# obc-v2_POWER.net
KiCad netlist of a schematic drawn in Altium Designer
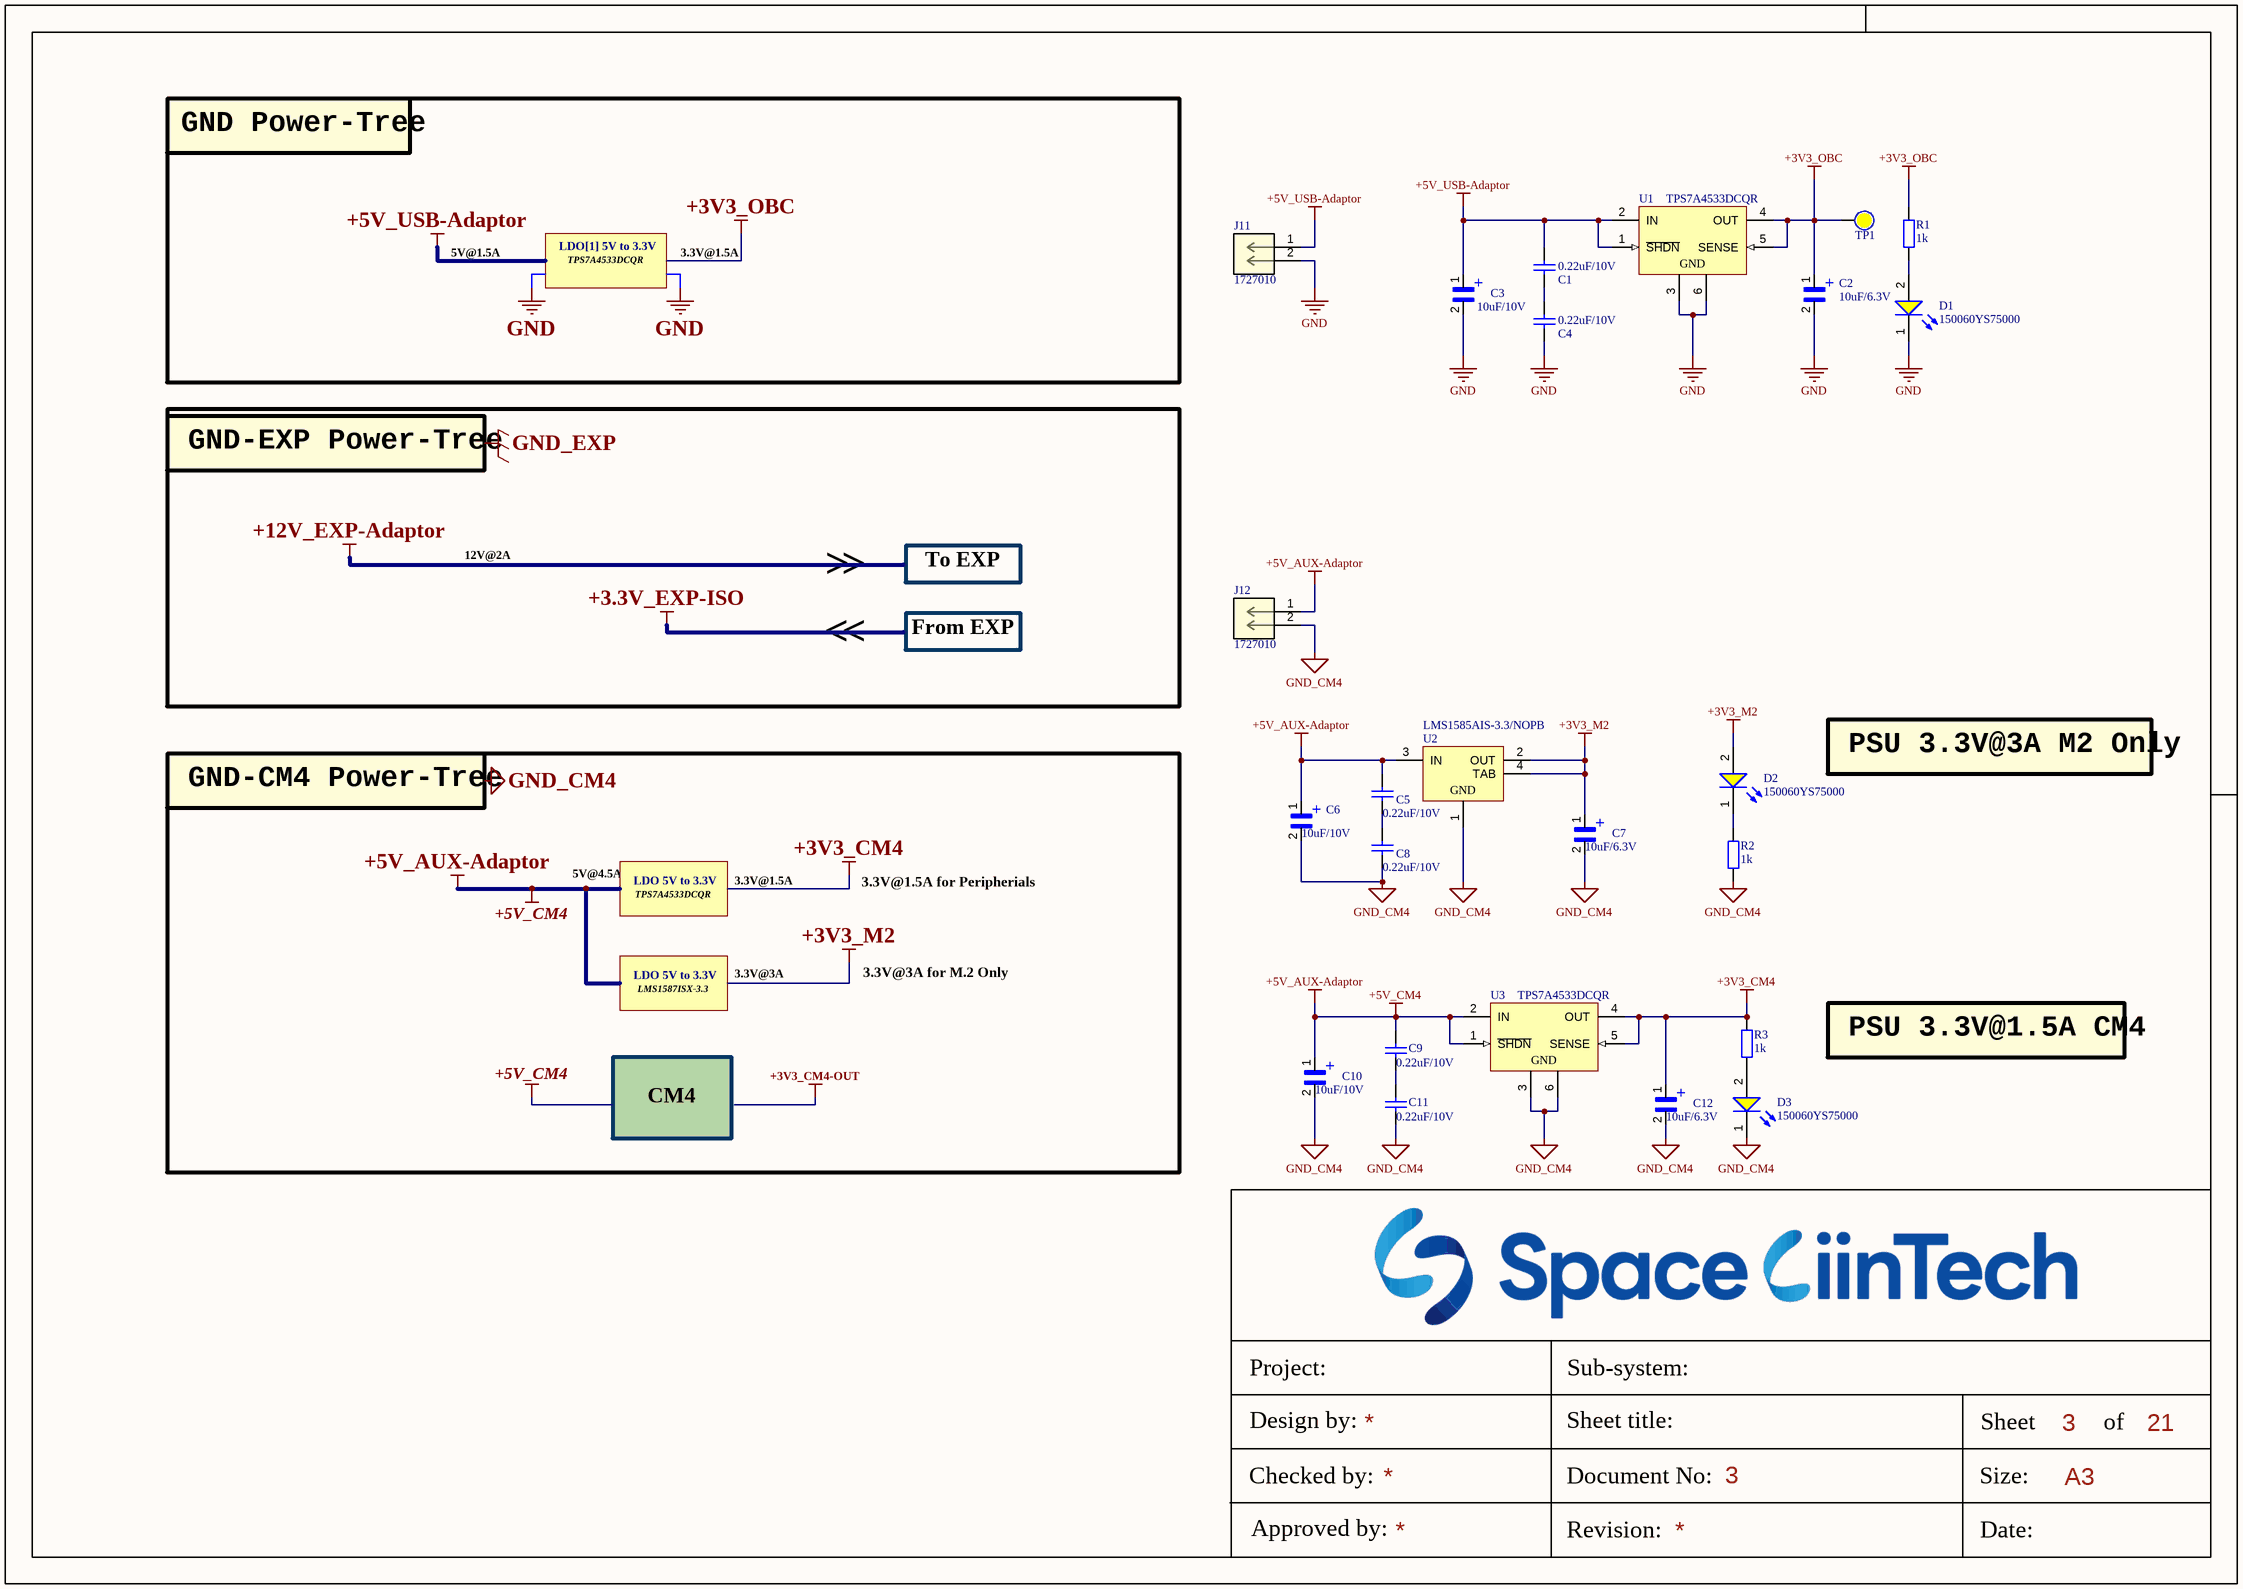
[diagram p0: obc-v2_POWER.SchDoc]

(export (version "E")
  (design (tool "Eeschema 10.0.6"))
  (components
    (comp (ref "C1")
      (value "0.22uF/10V")
      (footprint "CAP_C_1005X60")
      (description "CAPC")
      (libsource (lib "Altium_Lib_by_KhueNguyenCreator") (part "Tu 0402 33nF 10V"))
    )
    (comp (ref "C2")
      (value "10uF/6.3V")
      (footprint "CAP_MP_2012X170")
      (description "CAPP")
      (fields (field (name "MP") "TACR686M003RTA") (field (name "MF") "AVX"))
      (libsource (lib "TACR686M003RTA") (part "TACR686M003RTA"))
    )
    (comp (ref "C3")
      (value "10uF/10V")
      (footprint "CAP_MP_2012X170")
      (description "CAPP")
      (fields (field (name "MP") "TACR686M003RTA") (field (name "MF") "AVX"))
      (libsource (lib "TACR686M003RTA") (part "TACR686M003RTA"))
    )
    (comp (ref "C4")
      (value "0.22uF/10V")
      (footprint "CAP_C_1005X60")
      (description "CAPC")
      (libsource (lib "Altium_Lib_by_KhueNguyenCreator") (part "Tu 0402 33nF 10V"))
    )
    (comp (ref "C5")
      (value "0.22uF/10V")
      (footprint "CAP_C_1005X60")
      (description "CAPC")
      (libsource (lib "Altium_Lib_by_KhueNguyenCreator") (part "Tu 0402 33nF 10V"))
    )
    (comp (ref "C6")
      (value "10uF/10V")
      (footprint "CAP_MP_2012X170")
      (description "CAPP")
      (fields (field (name "MP") "TACR686M003RTA") (field (name "MF") "AVX"))
      (libsource (lib "TACR686M003RTA") (part "TACR686M003RTA"))
    )
    (comp (ref "C7")
      (value "10uF/6.3V")
      (footprint "CAP_MP_2012X170")
      (description "CAPP")
      (fields (field (name "MP") "TACR686M003RTA") (field (name "MF") "AVX"))
      (libsource (lib "TACR686M003RTA") (part "TACR686M003RTA"))
    )
    (comp (ref "C8")
      (value "0.22uF/10V")
      (footprint "CAP_C_1005X60")
      (description "CAPC")
      (libsource (lib "Altium_Lib_by_KhueNguyenCreator") (part "Tu 0402 33nF 10V"))
    )
    (comp (ref "C9")
      (value "0.22uF/10V")
      (footprint "CAP_C_1005X60")
      (description "CAPC")
      (libsource (lib "Altium_Lib_by_KhueNguyenCreator") (part "Tu 0402 33nF 10V"))
    )
    (comp (ref "C10")
      (value "10uF/10V")
      (footprint "CAP_MP_2012X170")
      (description "CAPP")
      (fields (field (name "MP") "TACR686M003RTA") (field (name "MF") "AVX"))
      (libsource (lib "TACR686M003RTA") (part "TACR686M003RTA"))
    )
    (comp (ref "C11")
      (value "0.22uF/10V")
      (footprint "CAP_C_1005X60")
      (description "CAPC")
      (libsource (lib "Altium_Lib_by_KhueNguyenCreator") (part "Tu 0402 33nF 10V"))
    )
    (comp (ref "C12")
      (value "10uF/6.3V")
      (footprint "CAP_MP_2012X170")
      (description "CAPP")
      (fields (field (name "MP") "TACR686M003RTA") (field (name "MF") "AVX"))
      (libsource (lib "TACR686M003RTA") (part "TACR686M003RTA"))
    )
    (comp (ref "D1")
      (value "150060YS75000")
      (footprint "WL-SMCW_0603_150060xx75000")
      (description "LED YELLOW CLEAR 0603 SMD")
      (libsource (lib "Altium Content Vault") (part "LED_Yellow_2A-1K"))
    )
    (comp (ref "D2")
      (value "150060YS75000")
      (footprint "WL-SMCW_0603_150060xx75000")
      (description "LED YELLOW CLEAR 0603 SMD")
      (libsource (lib "Altium Content Vault") (part "LED_Yellow_2A-1K"))
    )
    (comp (ref "D3")
      (value "150060YS75000")
      (footprint "WL-SMCW_0603_150060xx75000")
      (description "LED YELLOW CLEAR 0603 SMD")
      (libsource (lib "Altium Content Vault") (part "LED_Yellow_2A-1K"))
    )
    (comp (ref "J11")
      (value "1727010")
      (footprint "CONN_1727010")
      (description "No Description Available")
      (libsource (lib "obc_ver2") (part "1727010"))
    )
    (comp (ref "J12")
      (value "1727010")
      (footprint "CONN_1727010")
      (description "No Description Available")
      (libsource (lib "obc_ver2") (part "1727010"))
    )
    (comp (ref "R1")
      (value "1k")
      (footprint "RES_C_1608X60")
      (description "RES")
      (libsource (lib "Altium_Lib_by_KhueNguyenCreator") (part "Tro 0603 1% 10k"))
    )
    (comp (ref "R2")
      (value "1k")
      (footprint "RES_C_1608X60")
      (description "RES")
      (libsource (lib "Altium_Lib_by_KhueNguyenCreator") (part "Tro 0603 1% 10k"))
    )
    (comp (ref "R3")
      (value "1k")
      (footprint "RES_C_1608X60")
      (description "RES")
      (libsource (lib "Altium_Lib_by_KhueNguyenCreator") (part "Tro 0603 1% 10k"))
    )
    (comp (ref "TP1")
      (value "~")
      (footprint "Test Point 1 Side")
      (description "Test Point")
      (libsource (lib "BYTECH_HW_LIB_2019 (1)") (part "Test Point"))
    )
    (comp (ref "U1")
      (value "TPS7A4533DCQR")
      (footprint "DCQ0006A_M")
      (fields (field (name "MANUFACTURER") "Texas Instruments"))
      (libsource (lib "Altium Content Vault") (part "TI-TXXXXAXXXDCQ_KTTX"))
    )
    (comp (ref "U2")
      (value "LMS1585AIS-3.3/NOPB")
      (footprint "TS3B_L")
      (description "3A Low Dropout Fast Response Regulators, 3-pin TO-263, Pb-Free")
      (fields
        (field (name "PARTNUMBER") "LMS1587ISX-3.3/NOPB")
        (field (name "MANUFACTURER") "National Semiconductor")
      )
      (libsource (lib "Altium Content Vault") (part "PM-REG-LM1086-SOT4"))
    )
    (comp (ref "U3")
      (value "TPS7A4533DCQR")
      (footprint "DCQ0006A_M")
      (fields (field (name "MANUFACTURER") "Texas Instruments"))
      (libsource (lib "Altium Content Vault") (part "TI-TXXXXAXXXDCQ_KTTX"))
    )
  )
  (nets
    (net (code "2") (name "+3V3_CM4") (class "Default")
      (node (ref "C12") (pin "1") (pinfunction "1_1") (pintype "passive"))
      (node (ref "R3") (pin "2") (pinfunction "2_2") (pintype "passive"))
      (node (ref "U3") (pin "4") (pinfunction "OUT_4") (pintype "power_in"))
      (node (ref "U3") (pin "5") (pinfunction "SENSE_5") (pintype "input"))
    )
    (net (code "4") (name "+3V3_M2") (class "Default")
      (node (ref "C7") (pin "1") (pinfunction "1_1") (pintype "passive"))
      (node (ref "D2") (pin "2") (pinfunction "A_2") (pintype "passive"))
      (node (ref "U2") (pin "2") (pinfunction "OUT_2") (pintype "power_in"))
      (node (ref "U2") (pin "4") (pinfunction "TAB_4") (pintype "power_in"))
    )
    (net (code "5") (name "+3V3_OBC") (class "Default")
      (node (ref "C2") (pin "1") (pinfunction "1_1") (pintype "passive"))
      (node (ref "R1") (pin "2") (pinfunction "2_2") (pintype "passive"))
      (node (ref "TP1") (pin "0") (pinfunction "0_0") (pintype "passive"))
      (node (ref "U1") (pin "4") (pinfunction "OUT_4") (pintype "power_in"))
      (node (ref "U1") (pin "5") (pinfunction "SENSE_5") (pintype "input"))
    )
    (net (code "6") (name "+5V_AUX-Adaptor") (class "Default")
      (node (ref "C10") (pin "1") (pinfunction "1_1") (pintype "passive"))
      (node (ref "C5") (pin "1") (pinfunction "1_1") (pintype "passive"))
      (node (ref "C6") (pin "1") (pinfunction "1_1") (pintype "passive"))
      (node (ref "C9") (pin "1") (pinfunction "1_1") (pintype "passive"))
      (node (ref "J12") (pin "1") (pinfunction "1_1") (pintype "passive"))
      (node (ref "U2") (pin "3") (pinfunction "IN_3") (pintype "power_in"))
      (node (ref "U3") (pin "1") (pinfunction "~{SHDN}_1") (pintype "input"))
      (node (ref "U3") (pin "2") (pinfunction "IN_2") (pintype "power_in"))
    )
    (net (code "7") (name "+5V_USB-Adaptor") (class "Default")
      (node (ref "C1") (pin "1") (pinfunction "1_1") (pintype "passive"))
      (node (ref "C3") (pin "1") (pinfunction "1_1") (pintype "passive"))
      (node (ref "J11") (pin "1") (pinfunction "1_1") (pintype "passive"))
      (node (ref "U1") (pin "1") (pinfunction "~{SHDN}_1") (pintype "input"))
      (node (ref "U1") (pin "2") (pinfunction "IN_2") (pintype "power_in"))
    )
    (net (code "9") (name "GND") (class "Default")
      (node (ref "C2") (pin "2") (pinfunction "2_2") (pintype "passive"))
      (node (ref "C3") (pin "2") (pinfunction "2_2") (pintype "passive"))
      (node (ref "C4") (pin "2") (pinfunction "2_2") (pintype "passive"))
      (node (ref "D1") (pin "1") (pinfunction "K_1") (pintype "passive"))
      (node (ref "J11") (pin "2") (pinfunction "2_2") (pintype "passive"))
      (node (ref "U1") (pin "3") (pinfunction "GND_3") (pintype "power_in"))
      (node (ref "U1") (pin "6") (pinfunction "GND_6") (pintype "power_in"))
    )
    (net (code "10") (name "GND_CM4") (class "Default")
      (node (ref "C10") (pin "2") (pinfunction "2_2") (pintype "passive"))
      (node (ref "C11") (pin "2") (pinfunction "2_2") (pintype "passive"))
      (node (ref "C12") (pin "2") (pinfunction "2_2") (pintype "passive"))
      (node (ref "C6") (pin "2") (pinfunction "2_2") (pintype "passive"))
      (node (ref "C7") (pin "2") (pinfunction "2_2") (pintype "passive"))
      (node (ref "C8") (pin "2") (pinfunction "2_2") (pintype "passive"))
      (node (ref "D3") (pin "1") (pinfunction "K_1") (pintype "passive"))
      (node (ref "J12") (pin "2") (pinfunction "2_2") (pintype "passive"))
      (node (ref "R2") (pin "2") (pinfunction "2_2") (pintype "passive"))
      (node (ref "U2") (pin "1") (pinfunction "GND_1") (pintype "power_in"))
      (node (ref "U3") (pin "3") (pinfunction "GND_3") (pintype "power_in"))
      (node (ref "U3") (pin "6") (pinfunction "GND_6") (pintype "power_in"))
    )
    (net (code "12") (name "Net-(C1-Pad2)") (class "Default")
      (node (ref "C1") (pin "2") (pinfunction "2_2") (pintype "passive"))
      (node (ref "C4") (pin "1") (pinfunction "1_1") (pintype "passive"))
    )
    (net (code "13") (name "Net-(C5-Pad2)") (class "Default")
      (node (ref "C5") (pin "2") (pinfunction "2_2") (pintype "passive"))
      (node (ref "C8") (pin "1") (pinfunction "1_1") (pintype "passive"))
    )
    (net (code "14") (name "Net-(C11-Pad1)") (class "Default")
      (node (ref "C11") (pin "1") (pinfunction "1_1") (pintype "passive"))
      (node (ref "C9") (pin "2") (pinfunction "2_2") (pintype "passive"))
    )
    (net (code "15") (name "Net-(D1-A)") (class "Default")
      (node (ref "D1") (pin "2") (pinfunction "A_2") (pintype "passive"))
      (node (ref "R1") (pin "1") (pinfunction "1_1") (pintype "passive"))
    )
    (net (code "16") (name "Net-(D2-K)") (class "Default")
      (node (ref "D2") (pin "1") (pinfunction "K_1") (pintype "passive"))
      (node (ref "R2") (pin "1") (pinfunction "1_1") (pintype "passive"))
    )
    (net (code "17") (name "Net-(D3-A)") (class "Default")
      (node (ref "D3") (pin "2") (pinfunction "A_2") (pintype "passive"))
      (node (ref "R3") (pin "1") (pinfunction "1_1") (pintype "passive"))
    )
  )
)
